# YiyoLinkCC1111BMD200.net
KiCad netlist of a schematic drawn in EAGLE
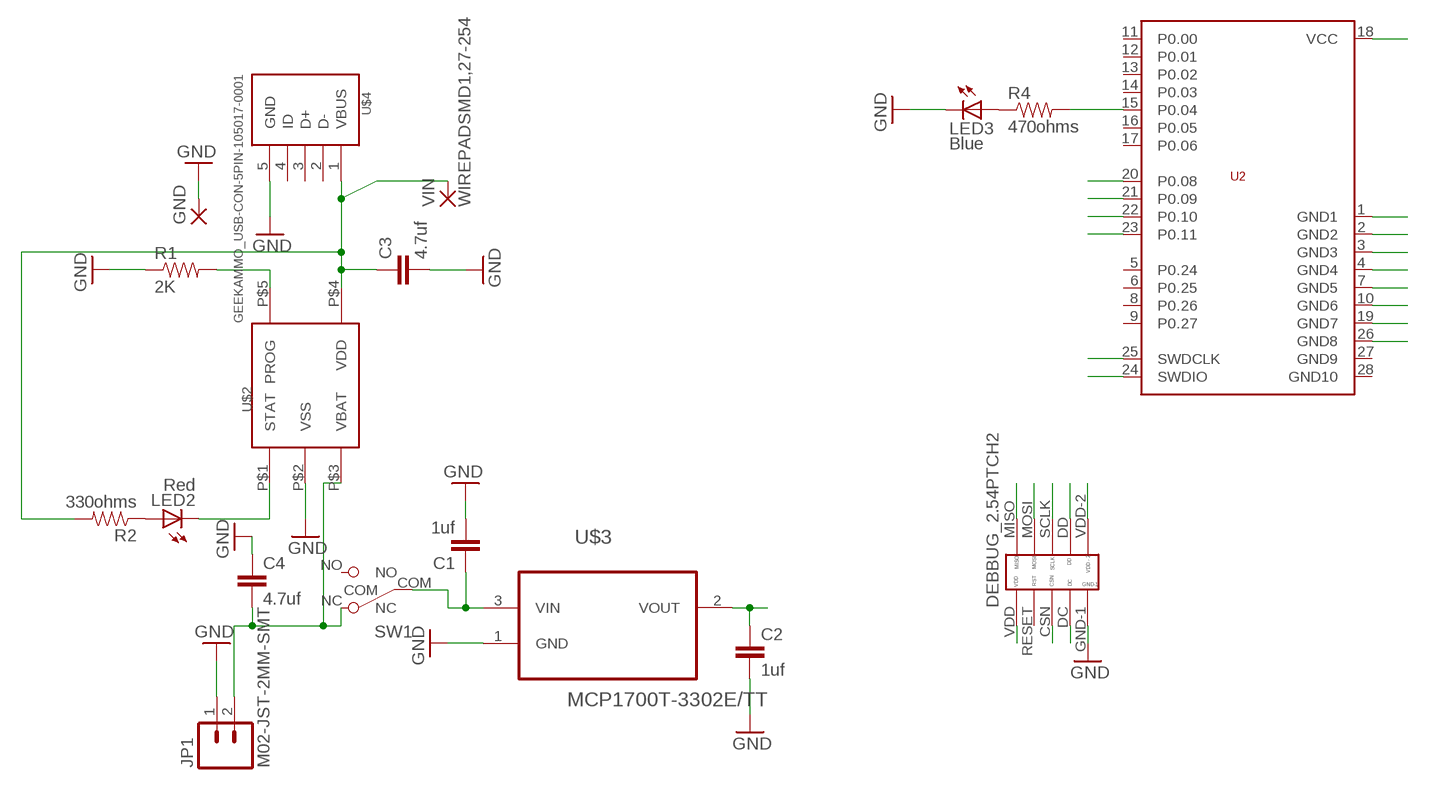
[diagram p0: schematic, sheet 1]

(export (version "E")
  (design (tool "Eeschema 10.0.6"))
  (components
    (comp (ref "C1")
      (value "1uf")
      (footprint "eagle-import:0805-CAP")
      (libsource (lib "eagle-import") (part "1UF-25V-10%(0805){dblquote}"))
    )
    (comp (ref "C2")
      (value "1uf")
      (footprint "eagle-import:0805-CAP")
      (libsource (lib "eagle-import") (part "1UF-25V-10%(0805){dblquote}"))
    )
    (comp (ref "C3")
      (value "4.7uf")
      (footprint "eagle-import:0805")
      (libsource (lib "eagle-import") (part "CAP0805"))
    )
    (comp (ref "C4")
      (value "4.7uf")
      (footprint "eagle-import:0805")
      (libsource (lib "eagle-import") (part "CAP0805"))
    )
    (comp (ref "DEBBUG_2.54PTCH2")
      (value "YIYOSLIBRARY_5X2_HEADER")
      (footprint "eagle-import:YIYOSLIBRARY_5X2_FEMALE_HEADER")
      (libsource (lib "eagle-import") (part "YIYOSLIBRARY_5X2_HEADER"))
    )
    (comp (ref "GND")
      (value "WIREPADSMD1,27-254")
      (footprint "eagle-import:SMD1,27-2,54")
      (libsource (lib "eagle-import") (part "WIREPADSMD1,27-254"))
    )
    (comp (ref "JP1")
      (value "M02-JST-2MM-SMT")
      (footprint "eagle-import:JST-2-SMD")
      (libsource (lib "eagle-import") (part "M02-JST-2MM-SMT"))
    )
    (comp (ref "LED2")
      (value "Red")
      (footprint "eagle-import:SML0805")
      (libsource (lib "eagle-import") (part "LEDSML0805"))
    )
    (comp (ref "LED3")
      (value "Blue")
      (footprint "eagle-import:SML0805")
      (libsource (lib "eagle-import") (part "LEDSML0805"))
    )
    (comp (ref "R1")
      (value "2K")
      (footprint "eagle-import:0805")
      (libsource (lib "eagle-import") (part "RESISTOR0805-RES"))
    )
    (comp (ref "R2")
      (value "330ohms")
      (footprint "eagle-import:0805")
      (libsource (lib "eagle-import") (part "RESISTOR0805-RES"))
    )
    (comp (ref "R4")
      (value "470ohms")
      (footprint "eagle-import:0805")
      (libsource (lib "eagle-import") (part "RESISTOR0805-RES"))
    )
    (comp (ref "SW1")
      (value "SW_SLIDE")
      (footprint "eagle-import:SLIDE_SWITCH_SMD")
      (libsource (lib "eagle-import") (part "SW_SLIDE"))
    )
    (comp (ref "U$2")
      (value "MCP73831")
      (footprint "eagle-import:5PIN_SOT23")
      (libsource (lib "eagle-import") (part "MCP73831"))
    )
    (comp (ref "U$3")
      (value "MCP1700T-3302E/TT")
      (footprint "eagle-import:SOT95P237X112-3N")
      (libsource (lib "eagle-import") (part "MCP1700T-3302E/TT"))
    )
    (comp (ref "U$4")
      (value "GEEKAMMO_USB-CON-5PIN-105017-0001")
      (footprint "eagle-import:GEEKAMMO_USB-MICRO-MOLEX-105017-0001")
      (libsource (lib "eagle-import") (part "GEEKAMMO_USB-CON-5PIN-105017-0001"))
    )
    (comp (ref "U2")
      (value "BMD-200")
      (footprint "eagle-import:BMD-200")
      (libsource (lib "eagle-import") (part "BMD-200"))
    )
    (comp (ref "VIN")
      (value "WIREPADSMD1,27-254")
      (footprint "eagle-import:SMD1,27-2,54")
      (libsource (lib "eagle-import") (part "WIREPADSMD1,27-254"))
    )
  )
  (nets
    (net (code "1") (name "/CSN") (class "Default")
      (node (ref "DEBBUG_2.54PTCH2") (pin "CSN") (pinfunction "CSN_CSN") (pintype "bidirectional"))
      (node (ref "U2") (pin "20") (pinfunction "P0.08_20") (pintype "bidirectional"))
    )
    (net (code "2") (name "/DC") (class "Default")
      (node (ref "DEBBUG_2.54PTCH2") (pin "DC") (pinfunction "DC_DC") (pintype "bidirectional"))
      (node (ref "U2") (pin "25") (pinfunction "SWDCLK_25") (pintype "bidirectional"))
    )
    (net (code "3") (name "/DD") (class "Default")
      (node (ref "DEBBUG_2.54PTCH2") (pin "DD") (pinfunction "DD_DD") (pintype "bidirectional"))
      (node (ref "U2") (pin "24") (pinfunction "SWDIO_24") (pintype "bidirectional"))
    )
    (net (code "4") (name "/MISO") (class "Default")
      (node (ref "DEBBUG_2.54PTCH2") (pin "MISO") (pinfunction "MISO_MISO") (pintype "bidirectional"))
      (node (ref "U2") (pin "22") (pinfunction "P0.10_22") (pintype "bidirectional"))
    )
    (net (code "5") (name "/MOSI") (class "Default")
      (node (ref "DEBBUG_2.54PTCH2") (pin "MOSI") (pinfunction "MOSI_MOSI") (pintype "input"))
      (node (ref "U2") (pin "21") (pinfunction "P0.09_21") (pintype "bidirectional"))
    )
    (net (code "6") (name "/SCLK") (class "Default")
      (node (ref "DEBBUG_2.54PTCH2") (pin "SCLK") (pinfunction "SCLK_SCLK") (pintype "bidirectional"))
      (node (ref "U2") (pin "23") (pinfunction "P0.11_23") (pintype "bidirectional"))
    )
    (net (code "7") (name "/VDDO") (class "Default")
      (node (ref "C2") (pin "1") (pinfunction "1_1") (pintype "passive"))
      (node (ref "DEBBUG_2.54PTCH2") (pin "VDD") (pinfunction "VDD_VDD") (pintype "bidirectional"))
      (node (ref "DEBBUG_2.54PTCH2") (pin "VDD-2") (pinfunction "VDD-2_VDD-2") (pintype "power_in"))
      (node (ref "U$3") (pin "2") (pinfunction "VOUT_2") (pintype "output"))
      (node (ref "U2") (pin "18") (pinfunction "VCC_18") (pintype "bidirectional"))
    )
    (net (code "8") (name "GND") (class "Default")
      (node (ref "C1") (pin "2") (pinfunction "2_2") (pintype "passive"))
      (node (ref "C2") (pin "2") (pinfunction "2_2") (pintype "passive"))
      (node (ref "C3") (pin "2") (pinfunction "2_2") (pintype "passive"))
      (node (ref "C4") (pin "1") (pinfunction "1_1") (pintype "passive"))
      (node (ref "DEBBUG_2.54PTCH2") (pin "GND-1") (pinfunction "GND-1_GND-1") (pintype "power_in"))
      (node (ref "GND") (pin "1") (pinfunction "P_1") (pintype "passive"))
      (node (ref "JP1") (pin "1") (pinfunction "2_1") (pintype "passive"))
      (node (ref "LED3") (pin "C") (pinfunction "C_C") (pintype "passive"))
      (node (ref "R1") (pin "1") (pinfunction "1_1") (pintype "passive"))
      (node (ref "U$2") (pin "P$2") (pinfunction "VSS_P$2") (pintype "bidirectional"))
      (node (ref "U$3") (pin "1") (pinfunction "GND_1") (pintype "passive"))
      (node (ref "U$4") (pin "5") (pinfunction "GND_5") (pintype "power_in"))
      (node (ref "U2") (pin "1") (pinfunction "GND1_1") (pintype "bidirectional"))
      (node (ref "U2") (pin "10") (pinfunction "GND6_10") (pintype "bidirectional"))
      (node (ref "U2") (pin "19") (pinfunction "GND7_19") (pintype "bidirectional"))
      (node (ref "U2") (pin "2") (pinfunction "GND2_2") (pintype "bidirectional"))
      (node (ref "U2") (pin "26") (pinfunction "GND8_26") (pintype "bidirectional"))
      (node (ref "U2") (pin "3") (pinfunction "GND3_3") (pintype "bidirectional"))
      (node (ref "U2") (pin "4") (pinfunction "GND4_4") (pintype "bidirectional"))
      (node (ref "U2") (pin "7") (pinfunction "GND5_7") (pintype "bidirectional"))
    )
    (net (code "9") (name "Net-(JP1-1)") (class "Default")
      (node (ref "C4") (pin "2") (pinfunction "2_2") (pintype "passive"))
      (node (ref "JP1") (pin "2") (pinfunction "1_2") (pintype "passive"))
      (node (ref "SW1") (pin "NC") (pinfunction "NC_NC") (pintype "passive"))
      (node (ref "U$2") (pin "P$3") (pinfunction "VBAT_P$3") (pintype "bidirectional"))
    )
    (net (code "10") (name "Net-(LED2-PadA)") (class "Default")
      (node (ref "LED2") (pin "A") (pinfunction "A_A") (pintype "passive"))
      (node (ref "R2") (pin "1") (pinfunction "1_1") (pintype "passive"))
    )
    (net (code "11") (name "Net-(LED3-PadA)") (class "Default")
      (node (ref "LED3") (pin "A") (pinfunction "A_A") (pintype "passive"))
      (node (ref "R4") (pin "1") (pinfunction "1_1") (pintype "passive"))
    )
    (net (code "12") (name "Net-(U$2-PROG)") (class "Default")
      (node (ref "R1") (pin "2") (pinfunction "2_2") (pintype "passive"))
      (node (ref "U$2") (pin "P$5") (pinfunction "PROG_P$5") (pintype "bidirectional"))
    )
    (net (code "13") (name "Net-(U$2-STAT)") (class "Default")
      (node (ref "LED2") (pin "C") (pinfunction "C_C") (pintype "passive"))
      (node (ref "U$2") (pin "P$1") (pinfunction "STAT_P$1") (pintype "bidirectional"))
    )
    (net (code "14") (name "Net-(U$2-VDD)") (class "Default")
      (node (ref "C3") (pin "1") (pinfunction "1_1") (pintype "passive"))
      (node (ref "R2") (pin "2") (pinfunction "2_2") (pintype "passive"))
      (node (ref "U$2") (pin "P$4") (pinfunction "VDD_P$4") (pintype "bidirectional"))
      (node (ref "U$4") (pin "1") (pinfunction "VBUS_1") (pintype "power_in"))
      (node (ref "VIN") (pin "1") (pinfunction "P_1") (pintype "passive"))
    )
    (net (code "15") (name "Net-(U$3-VIN)") (class "Default")
      (node (ref "C1") (pin "1") (pinfunction "1_1") (pintype "passive"))
      (node (ref "SW1") (pin "COM") (pinfunction "COM_COM") (pintype "passive"))
      (node (ref "U$3") (pin "3") (pinfunction "VIN_3") (pintype "input"))
    )
    (net (code "16") (name "Net-(U2-P0.04)") (class "Default")
      (node (ref "R4") (pin "2") (pinfunction "2_2") (pintype "passive"))
      (node (ref "U2") (pin "15") (pinfunction "P0.04_15") (pintype "bidirectional"))
    )
    (net (code "17") (name "unconnected-(DEBBUG_2.54PTCH2-RST-PadRESET)") (class "Default")
      (node (ref "DEBBUG_2.54PTCH2") (pin "RESET") (pinfunction "RST_RESET") (pintype "bidirectional"))
    )
    (net (code "18") (name "unconnected-(SW1-PadNO)") (class "Default")
      (node (ref "SW1") (pin "NO") (pinfunction "NO_NO") (pintype "passive"))
    )
    (net (code "19") (name "unconnected-(U$4-D+-Pad3)") (class "Default")
      (node (ref "U$4") (pin "3") (pinfunction "D+_3") (pintype "bidirectional"))
    )
    (net (code "20") (name "unconnected-(U$4-D--Pad2)") (class "Default")
      (node (ref "U$4") (pin "2") (pinfunction "D-_2") (pintype "bidirectional"))
    )
    (net (code "21") (name "unconnected-(U$4-ID-Pad4)") (class "Default")
      (node (ref "U$4") (pin "4") (pinfunction "ID_4") (pintype "bidirectional"))
    )
    (net (code "22") (name "unconnected-(U2-GND9-Pad27)") (class "Default")
      (node (ref "U2") (pin "27") (pinfunction "GND9_27") (pintype "bidirectional"))
    )
    (net (code "23") (name "unconnected-(U2-GND10-Pad28)") (class "Default")
      (node (ref "U2") (pin "28") (pinfunction "GND10_28") (pintype "bidirectional"))
    )
    (net (code "24") (name "unconnected-(U2-P0.00-Pad11)") (class "Default")
      (node (ref "U2") (pin "11") (pinfunction "P0.00_11") (pintype "bidirectional"))
    )
    (net (code "25") (name "unconnected-(U2-P0.01-Pad12)") (class "Default")
      (node (ref "U2") (pin "12") (pinfunction "P0.01_12") (pintype "bidirectional"))
    )
    (net (code "26") (name "unconnected-(U2-P0.02-Pad13)") (class "Default")
      (node (ref "U2") (pin "13") (pinfunction "P0.02_13") (pintype "bidirectional"))
    )
    (net (code "27") (name "unconnected-(U2-P0.03-Pad14)") (class "Default")
      (node (ref "U2") (pin "14") (pinfunction "P0.03_14") (pintype "bidirectional"))
    )
    (net (code "28") (name "unconnected-(U2-P0.05-Pad16)") (class "Default")
      (node (ref "U2") (pin "16") (pinfunction "P0.05_16") (pintype "bidirectional"))
    )
    (net (code "29") (name "unconnected-(U2-P0.06-Pad17)") (class "Default")
      (node (ref "U2") (pin "17") (pinfunction "P0.06_17") (pintype "bidirectional"))
    )
    (net (code "30") (name "unconnected-(U2-P0.24-Pad5)") (class "Default")
      (node (ref "U2") (pin "5") (pinfunction "P0.24_5") (pintype "bidirectional"))
    )
    (net (code "31") (name "unconnected-(U2-P0.25-Pad6)") (class "Default")
      (node (ref "U2") (pin "6") (pinfunction "P0.25_6") (pintype "bidirectional"))
    )
    (net (code "32") (name "unconnected-(U2-P0.26-Pad8)") (class "Default")
      (node (ref "U2") (pin "8") (pinfunction "P0.26_8") (pintype "bidirectional"))
    )
    (net (code "33") (name "unconnected-(U2-P0.27-Pad9)") (class "Default")
      (node (ref "U2") (pin "9") (pinfunction "P0.27_9") (pintype "bidirectional"))
    )
  )
)
